# connector_temp_level.net
KiCad netlist of a schematic drawn in Altium Designer
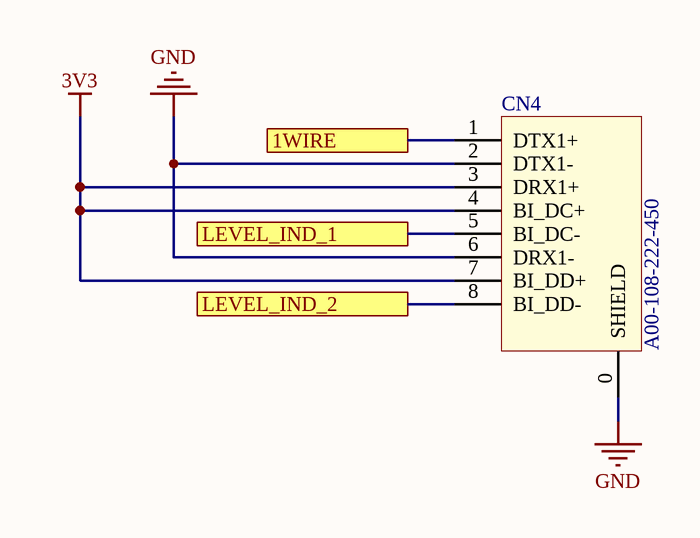
[diagram p0: connector_temp_level.SchDoc]

(export (version "E")
  (design (tool "Eeschema 10.0.6"))
  (components
    (comp (ref "CN4")
      (value "CONN_RJ45_TOP_A00-108-222-450")
      (footprint "RJ45 TOP ENTRY EDAC A00-108-222-450")
      (description "CONN, RJ-45, 1-PORT, 8-POS, VERT, 0.76um GOLD, TH")
      (fields (field (name "MFG") "EDAC Inc") (field (name "MFG P/N") "A00-108-222-450"))
      (libsource (lib "AltiumReleaseLibDB") (part "CONN_RJ45_TOP_A00-108-222-450"))
    )
  )
  (nets
    (net (code "1") (name "/1WIRE") (class "Default")
      (node (ref "CN4") (pin "1") (pinfunction "DTX1+_1") (pintype "passive"))
    )
    (net (code "2") (name "/LEVEL_IND_1") (class "Default")
      (node (ref "CN4") (pin "5") (pinfunction "BI_DC-_5") (pintype "passive"))
    )
    (net (code "3") (name "/LEVEL_IND_2") (class "Default")
      (node (ref "CN4") (pin "8") (pinfunction "BI_DD-_8") (pintype "passive"))
    )
    (net (code "4") (name "3V3") (class "Default")
      (node (ref "CN4") (pin "3") (pinfunction "DRX1+_3") (pintype "passive"))
      (node (ref "CN4") (pin "4") (pinfunction "BI_DC+_4") (pintype "passive"))
      (node (ref "CN4") (pin "7") (pinfunction "BI_DD+_7") (pintype "passive"))
    )
    (net (code "5") (name "GND") (class "Default")
      (node (ref "CN4") (pin "0") (pinfunction "SHIELD_0") (pintype "passive"))
      (node (ref "CN4") (pin "2") (pinfunction "DTX1-_2") (pintype "passive"))
      (node (ref "CN4") (pin "6") (pinfunction "DRX1-_6") (pintype "passive"))
    )
  )
)
